# havits_crawdaff.net
KiCad netlist of a schematic drawn in EAGLE
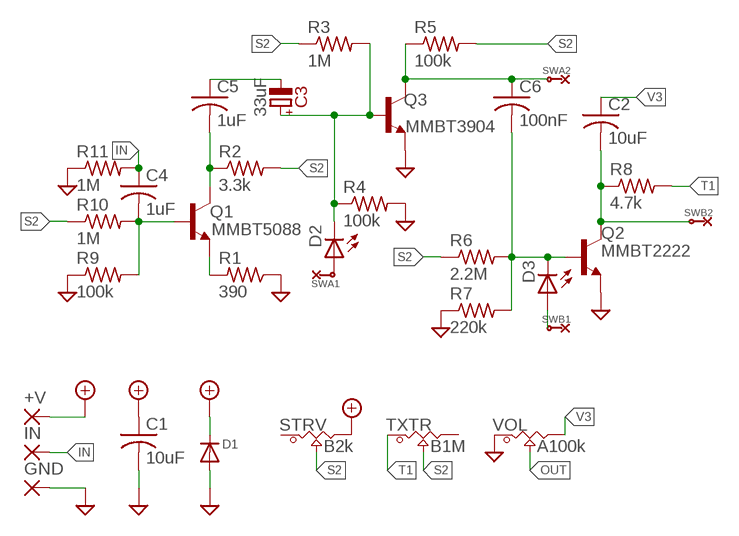
[diagram p0: schematic, sheet 1]

(export (version "E")
  (design (tool "Eeschema 10.0.6"))
  (components
    (comp (ref "+V")
      (value "SMD2")
      (footprint "eagle-import:SMD1,27-2,54")
      (libsource (lib "eagle-import") (part "SMD2"))
    )
    (comp (ref "C1")
      (value "10uF")
      (footprint "eagle-import:C1206")
      (libsource (lib "eagle-import") (part "C-USC1206"))
    )
    (comp (ref "C2")
      (value "10uF")
      (footprint "eagle-import:C1206")
      (libsource (lib "eagle-import") (part "C-USC1206"))
    )
    (comp (ref "C3")
      (value "33uF")
      (footprint "eagle-import:PAN_B")
      (libsource (lib "eagle-import") (part "PAN_B"))
    )
    (comp (ref "C4")
      (value "1uF")
      (footprint "eagle-import:C0603")
      (libsource (lib "eagle-import") (part "C-USC0603"))
    )
    (comp (ref "C5")
      (value "1uF")
      (footprint "eagle-import:C0603")
      (libsource (lib "eagle-import") (part "C-USC0603"))
    )
    (comp (ref "C6")
      (value "100nF")
      (footprint "eagle-import:C0603")
      (libsource (lib "eagle-import") (part "C-USC0603"))
    )
    (comp (ref "D1")
      (value "DIODESOD-123")
      (footprint "eagle-import:SOD-123")
      (libsource (lib "eagle-import") (part "DIODESOD-123"))
    )
    (comp (ref "D2")
      (value "LEDCHIPLED_0603")
      (footprint "eagle-import:CHIPLED_0603")
      (libsource (lib "eagle-import") (part "LEDCHIPLED_0603"))
    )
    (comp (ref "D3")
      (value "LEDCHIPLED_0603")
      (footprint "eagle-import:CHIPLED_0603")
      (libsource (lib "eagle-import") (part "LEDCHIPLED_0603"))
    )
    (comp (ref "GND")
      (value "SMD2")
      (footprint "eagle-import:SMD1,27-2,54")
      (libsource (lib "eagle-import") (part "SMD2"))
    )
    (comp (ref "IN")
      (value "SMD2")
      (footprint "eagle-import:SMD1,27-2,54")
      (libsource (lib "eagle-import") (part "SMD2"))
    )
    (comp (ref "Q1")
      (value "MMBT5088")
      (footprint "eagle-import:SOT23-BEC")
      (fields (field (name "MF") "ON Semiconductor"))
      (libsource (lib "eagle-import") (part "MMBT5088"))
    )
    (comp (ref "Q2")
      (value "MMBT2222")
      (footprint "eagle-import:SOT23-BEC")
      (libsource (lib "eagle-import") (part "-NPN-SOT23-BECMMBT2222ALT1"))
    )
    (comp (ref "Q3")
      (value "MMBT3904")
      (footprint "eagle-import:SOT23-3")
      (fields
        (field (name "DIGIKEY_PART_NUMBER") "MMBT3904LT1GOSTR-ND")
        (field (name "MANUFACTURER") "ON Semiconductor")
        (field (name "MPN") "MMBT3904LT1G")
        (field (name "CREATED_BY") "PCBLayout.com")
      )
      (libsource (lib "eagle-import") (part "MMBT3904LT1G"))
    )
    (comp (ref "R1")
      (value "390")
      (footprint "eagle-import:R0603")
      (libsource (lib "eagle-import") (part "R-US_R0603"))
    )
    (comp (ref "R2")
      (value "3.3k")
      (footprint "eagle-import:R0603")
      (libsource (lib "eagle-import") (part "R-US_R0603"))
    )
    (comp (ref "R3")
      (value "1M")
      (footprint "eagle-import:R0603")
      (libsource (lib "eagle-import") (part "R-US_R0603"))
    )
    (comp (ref "R4")
      (value "100k")
      (footprint "eagle-import:R0603")
      (libsource (lib "eagle-import") (part "R-US_R0603"))
    )
    (comp (ref "R5")
      (value "100k")
      (footprint "eagle-import:R0603")
      (libsource (lib "eagle-import") (part "R-US_R0603"))
    )
    (comp (ref "R6")
      (value "2.2M")
      (footprint "eagle-import:R0603")
      (libsource (lib "eagle-import") (part "R-US_R0603"))
    )
    (comp (ref "R7")
      (value "220k")
      (footprint "eagle-import:R0603")
      (libsource (lib "eagle-import") (part "R-US_R0603"))
    )
    (comp (ref "R8")
      (value "4.7k")
      (footprint "eagle-import:R0603")
      (libsource (lib "eagle-import") (part "R-US_R0603"))
    )
    (comp (ref "R9")
      (value "100k")
      (footprint "eagle-import:R0603")
      (libsource (lib "eagle-import") (part "R-US_R0603"))
    )
    (comp (ref "R10")
      (value "1M")
      (footprint "eagle-import:R0603")
      (libsource (lib "eagle-import") (part "R-US_R0603"))
    )
    (comp (ref "R11")
      (value "1M")
      (footprint "eagle-import:R0603")
      (libsource (lib "eagle-import") (part "R-US_R0603"))
    )
    (comp (ref "STRV")
      (value "B2k")
      (footprint "eagle-import:POT_9MM_SMD")
      (libsource (lib "eagle-import") (part "POT_9MM_SMD"))
    )
    (comp (ref "SWA1")
      (value "COM_SMD")
      (footprint "eagle-import:1PAD")
      (libsource (lib "eagle-import") (part "COM_SMD"))
    )
    (comp (ref "SWA2")
      (value "COM_SMD")
      (footprint "eagle-import:1PAD")
      (libsource (lib "eagle-import") (part "COM_SMD"))
    )
    (comp (ref "SWB1")
      (value "COM_SMD")
      (footprint "eagle-import:1PAD")
      (libsource (lib "eagle-import") (part "COM_SMD"))
    )
    (comp (ref "SWB2")
      (value "COM_SMD")
      (footprint "eagle-import:1PAD")
      (libsource (lib "eagle-import") (part "COM_SMD"))
    )
    (comp (ref "TXTR")
      (value "B1M")
      (footprint "eagle-import:POT_9MM_SMD")
      (libsource (lib "eagle-import") (part "POT_9MM_SMD"))
    )
    (comp (ref "VOL")
      (value "A100k")
      (footprint "eagle-import:POT_9MM_SMD")
      (libsource (lib "eagle-import") (part "POT_9MM_SMD"))
    )
  )
  (nets
    (net (code "1") (name "+9V") (class "Default")
      (node (ref "+V") (pin "1") (pinfunction "P_1") (pintype "passive"))
      (node (ref "C1") (pin "1") (pinfunction "1_1") (pintype "passive"))
      (node (ref "D1") (pin "C") (pinfunction "C_C") (pintype "passive"))
      (node (ref "STRV") (pin "3") (pinfunction "3_3") (pintype "bidirectional"))
    )
    (net (code "2") (name "GND") (class "Default")
      (node (ref "C1") (pin "2") (pinfunction "2_2") (pintype "passive"))
      (node (ref "D1") (pin "A") (pinfunction "A_A") (pintype "passive"))
      (node (ref "GND") (pin "1") (pinfunction "P_1") (pintype "passive"))
      (node (ref "Q2") (pin "E") (pinfunction "E_E") (pintype "passive"))
      (node (ref "Q3") (pin "2") (pinfunction "E_2") (pintype "passive"))
      (node (ref "R1") (pin "1") (pinfunction "1_1") (pintype "passive"))
      (node (ref "R11") (pin "1") (pinfunction "1_1") (pintype "passive"))
      (node (ref "R4") (pin "2") (pinfunction "2_2") (pintype "passive"))
      (node (ref "R7") (pin "1") (pinfunction "1_1") (pintype "passive"))
      (node (ref "R9") (pin "1") (pinfunction "1_1") (pintype "passive"))
      (node (ref "VOL") (pin "1") (pinfunction "1_1") (pintype "bidirectional"))
    )
    (net (code "3") (name "IN") (class "Default")
      (node (ref "C4") (pin "1") (pinfunction "1_1") (pintype "passive"))
      (node (ref "IN") (pin "1") (pinfunction "P_1") (pintype "passive"))
      (node (ref "R11") (pin "2") (pinfunction "2_2") (pintype "passive"))
    )
    (net (code "4") (name "Net-(C2-Pad2)") (class "Default")
      (node (ref "C2") (pin "2") (pinfunction "2_2") (pintype "passive"))
      (node (ref "Q2") (pin "C") (pinfunction "C_C") (pintype "passive"))
      (node (ref "R8") (pin "1") (pinfunction "1_1") (pintype "passive"))
      (node (ref "SWB2") (pin "1") (pinfunction "1_1") (pintype "bidirectional"))
    )
    (net (code "5") (name "Net-(C3-+)") (class "Default")
      (node (ref "C3") (pin "1+") (pinfunction "+_1+") (pintype "passive"))
      (node (ref "D2") (pin "C") (pinfunction "C_C") (pintype "passive"))
      (node (ref "Q3") (pin "1") (pinfunction "B_1") (pintype "passive"))
      (node (ref "R3") (pin "2") (pinfunction "2_2") (pintype "passive"))
      (node (ref "R4") (pin "1") (pinfunction "1_1") (pintype "passive"))
    )
    (net (code "6") (name "Net-(C3--)") (class "Default")
      (node (ref "C3") (pin "2-") (pinfunction "-_2-") (pintype "passive"))
      (node (ref "C5") (pin "1") (pinfunction "1_1") (pintype "passive"))
    )
    (net (code "7") (name "Net-(C4-Pad2)") (class "Default")
      (node (ref "C4") (pin "2") (pinfunction "2_2") (pintype "passive"))
      (node (ref "Q1") (pin "B") (pinfunction "B_B") (pintype "passive"))
      (node (ref "R10") (pin "2") (pinfunction "2_2") (pintype "passive"))
      (node (ref "R9") (pin "2") (pinfunction "2_2") (pintype "passive"))
    )
    (net (code "8") (name "Net-(C5-Pad2)") (class "Default")
      (node (ref "C5") (pin "2") (pinfunction "2_2") (pintype "passive"))
      (node (ref "Q1") (pin "C") (pinfunction "C_C") (pintype "passive"))
      (node (ref "R2") (pin "1") (pinfunction "1_1") (pintype "passive"))
    )
    (net (code "9") (name "Net-(C6-Pad2)") (class "Default")
      (node (ref "C6") (pin "2") (pinfunction "2_2") (pintype "passive"))
      (node (ref "D3") (pin "C") (pinfunction "C_C") (pintype "passive"))
      (node (ref "Q2") (pin "B") (pinfunction "B_B") (pintype "passive"))
      (node (ref "R6") (pin "2") (pinfunction "2_2") (pintype "passive"))
      (node (ref "R7") (pin "2") (pinfunction "2_2") (pintype "passive"))
    )
    (net (code "10") (name "Net-(D2-PadA)") (class "Default")
      (node (ref "D2") (pin "A") (pinfunction "A_A") (pintype "passive"))
      (node (ref "SWA1") (pin "1") (pinfunction "1_1") (pintype "bidirectional"))
    )
    (net (code "11") (name "Net-(D3-PadA)") (class "Default")
      (node (ref "D3") (pin "A") (pinfunction "A_A") (pintype "passive"))
      (node (ref "SWB1") (pin "1") (pinfunction "1_1") (pintype "bidirectional"))
    )
    (net (code "12") (name "Net-(Q1-PadE)") (class "Default")
      (node (ref "Q1") (pin "E") (pinfunction "E_E") (pintype "passive"))
      (node (ref "R1") (pin "2") (pinfunction "2_2") (pintype "passive"))
    )
    (net (code "13") (name "Net-(Q3-C)") (class "Default")
      (node (ref "C6") (pin "1") (pinfunction "1_1") (pintype "passive"))
      (node (ref "Q3") (pin "3") (pinfunction "C_3") (pintype "passive"))
      (node (ref "R5") (pin "1") (pinfunction "1_1") (pintype "passive"))
      (node (ref "SWA2") (pin "1") (pinfunction "1_1") (pintype "bidirectional"))
    )
    (net (code "14") (name "OUT") (class "Default")
      (node (ref "VOL") (pin "2") (pinfunction "2_2") (pintype "bidirectional"))
    )
    (net (code "15") (name "S2") (class "Default")
      (node (ref "R10") (pin "1") (pinfunction "1_1") (pintype "passive"))
      (node (ref "R2") (pin "2") (pinfunction "2_2") (pintype "passive"))
      (node (ref "R3") (pin "1") (pinfunction "1_1") (pintype "passive"))
      (node (ref "R5") (pin "2") (pinfunction "2_2") (pintype "passive"))
      (node (ref "R6") (pin "1") (pinfunction "1_1") (pintype "passive"))
      (node (ref "STRV") (pin "2") (pinfunction "2_2") (pintype "bidirectional"))
      (node (ref "TXTR") (pin "2") (pinfunction "2_2") (pintype "bidirectional"))
    )
    (net (code "16") (name "T1") (class "Default")
      (node (ref "R8") (pin "2") (pinfunction "2_2") (pintype "passive"))
      (node (ref "TXTR") (pin "1") (pinfunction "1_1") (pintype "bidirectional"))
    )
    (net (code "17") (name "V3") (class "Default")
      (node (ref "C2") (pin "1") (pinfunction "1_1") (pintype "passive"))
      (node (ref "VOL") (pin "3") (pinfunction "3_3") (pintype "bidirectional"))
    )
    (net (code "18") (name "unconnected-(STRV-Pad1)") (class "Default")
      (node (ref "STRV") (pin "1") (pinfunction "1_1") (pintype "bidirectional"))
    )
    (net (code "19") (name "unconnected-(TXTR-Pad3)") (class "Default")
      (node (ref "TXTR") (pin "3") (pinfunction "3_3") (pintype "bidirectional"))
    )
  )
)
